# CLP_v1_2_Sch.net
KiCad netlist of a schematic drawn in Altium Designer
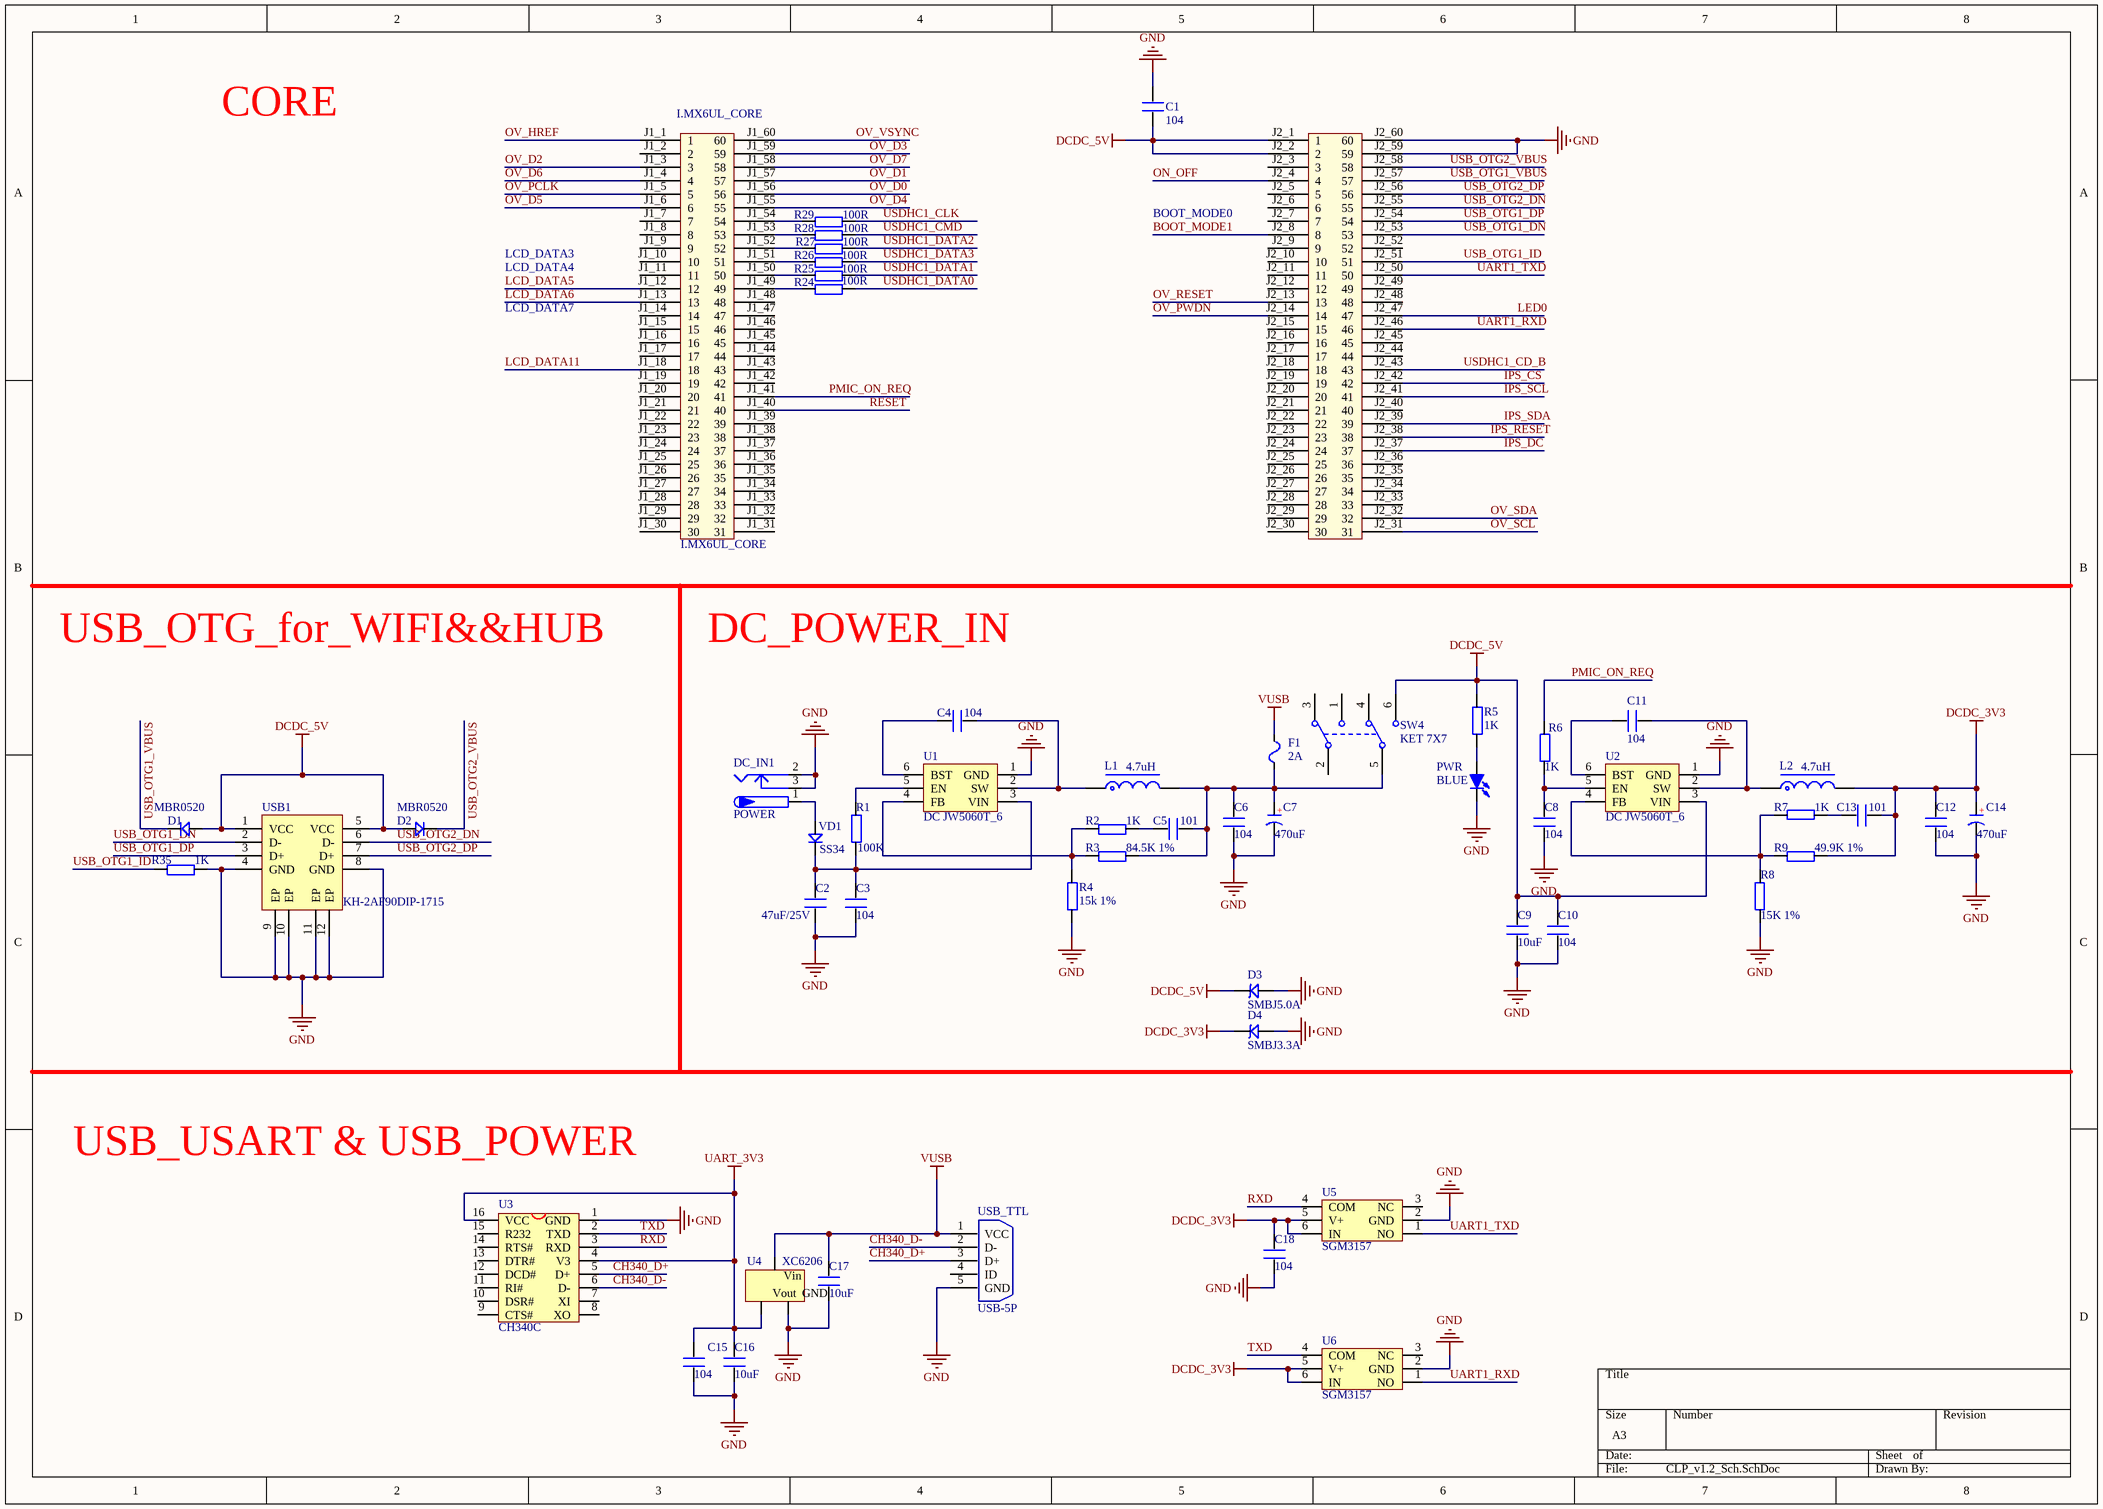
[diagram p0: CLP_v1.2_Sch.SchDoc]

(export (version "E")
  (design (tool "Eeschema 10.0.6"))
  (components
    (comp (ref "C1") (value "104") (footprint "C 0603") (libsource (lib "IMX6UL_ALPHA(底板)_V2.0") (part "C")))
    (comp (ref "C2")
      (value "47uF/25V")
      (footprint "1206")
      (libsource (lib "IMX6UL_ALPHA(底板)_V2.0") (part "C"))
    )
    (comp (ref "C3") (value "104") (footprint "C 0603") (libsource (lib "IMX6UL_ALPHA(底板)_V2.0") (part "C")))
    (comp (ref "C4") (value "104") (footprint "C 0603") (libsource (lib "IMX6UL_ALPHA(底板)_V2.0") (part "C")))
    (comp (ref "C5") (value "101") (footprint "C 0603") (libsource (lib "IMX6UL_ALPHA(底板)_V2.0") (part "C")))
    (comp (ref "C6") (value "104") (footprint "C 0603") (libsource (lib "IMX6UL_ALPHA(底板)_V2.0") (part "C")))
    (comp (ref "C7")
      (value "470uF")
      (footprint "CM D(6.3*7.7)")
      (description "贴片电解电容")
      (fields (field (name "版权归属") "源创客"))
      (libsource (lib "IMX6UL_ALPHA(底板)_V2.0") (part "C-CM"))
    )
    (comp (ref "C8") (value "104") (footprint "C 0603") (libsource (lib "IMX6UL_ALPHA(底板)_V2.0") (part "C")))
    (comp (ref "C9") (value "10uF") (footprint "C 0603") (libsource (lib "IMX6UL_ALPHA(底板)_V2.0") (part "C")))
    (comp (ref "C10") (value "104") (footprint "C 0603") (libsource (lib "IMX6UL_ALPHA(底板)_V2.0") (part "C")))
    (comp (ref "C11") (value "104") (footprint "C 0603") (libsource (lib "IMX6UL_ALPHA(底板)_V2.0") (part "C")))
    (comp (ref "C12") (value "104") (footprint "C 0603") (libsource (lib "IMX6UL_ALPHA(底板)_V2.0") (part "C")))
    (comp (ref "C13") (value "101") (footprint "C 0603") (libsource (lib "IMX6UL_ALPHA(底板)_V2.0") (part "C")))
    (comp (ref "C14")
      (value "470uF")
      (footprint "CM D(6.3*7.7)")
      (description "贴片电解电容")
      (fields (field (name "版权归属") "源创客"))
      (libsource (lib "IMX6UL_ALPHA(底板)_V2.0") (part "C-CM"))
    )
    (comp (ref "C15") (value "104") (footprint "C 0603") (libsource (lib "IMX6UL_ALPHA(底板)_V2.0") (part "C")))
    (comp (ref "C16")
      (value "10uF")
      (footprint "C 0603")
      (libsource (lib "IMX6UL_ALPHA(底板)_V2.0") (part "C"))
    )
    (comp (ref "C17")
      (value "10uF")
      (footprint "C 0603")
      (libsource (lib "IMX6UL_ALPHA(底板)_V2.0") (part "C"))
    )
    (comp (ref "C18") (value "104") (footprint "C 0603") (libsource (lib "IMX6UL_ALPHA(底板)_V2.0") (part "C")))
    (comp (ref "D1")
      (value "MBR0520")
      (footprint "SOD-123F")
      (description "肖特基二极管")
      (fields (field (name "版权归属") "源创客"))
      (libsource (lib "IMX6UL_ALPHA(底板)_V2.0") (part "SS14"))
    )
    (comp (ref "D2")
      (value "MBR0520")
      (footprint "SOD-123F")
      (description "肖特基二极管")
      (fields (field (name "版权归属") "源创客"))
      (libsource (lib "IMX6UL_ALPHA(底板)_V2.0") (part "SS14"))
    )
    (comp (ref "D3")
      (value "SMBJ5.0A")
      (footprint "SMBJ")
      (description "TVS")
      (libsource (lib "IMX6UL_ALPHA(底板)_V2.0") (part "SMBJ"))
    )
    (comp (ref "D4")
      (value "SMBJ3.3A")
      (footprint "SMBJ")
      (description "TVS")
      (libsource (lib "IMX6UL_ALPHA(底板)_V2.0") (part "SMBJ"))
    )
    (comp (ref "DC_IN1")
      (value "POWER")
      (footprint "DC10B")
      (description "低压电源接口")
      (fields (field (name "版权归属") "源创客"))
      (libsource (lib "IMX6UL_ALPHA(底板)_V2.0") (part "P-DC"))
    )
    (comp (ref "F1")
      (value "2A")
      (footprint "FU 1206")
      (description "贴片保险丝")
      (fields (field (name "版权归属") "源创客"))
      (libsource (lib "IMX6UL_ALPHA(底板)_V2.0") (part "FU"))
    )
    (comp (ref "I.MX6UL_CORE")
      (value "I.MX6UL_CORE")
      (footprint "I.MX6UL_CORE")
      (description "I.MX6UL核心板")
      (libsource (lib "IMX6UL_ALPHA(底板)_V2.0") (part "I.MX6UL核心板"))
    )
    (comp (ref "L1")
      (value "4.7uH")
      (footprint "L-SMD-0420")
      (description "功率屏蔽电感")
      (fields (field (name "版权归属") "源创客"))
      (libsource (lib "IMX6UL_ALPHA(底板)_V2.0") (part "L-CDRH"))
    )
    (comp (ref "L2")
      (value "4.7uH")
      (footprint "L-SMD-0420")
      (description "功率屏蔽电感")
      (fields (field (name "版权归属") "源创客"))
      (libsource (lib "IMX6UL_ALPHA(底板)_V2.0") (part "L-CDRH"))
    )
    (comp (ref "PWR")
      (value "BLUE")
      (footprint "LED 0805R")
      (description "贴片LED")
      (fields (field (name "版权归属") "源创客"))
      (libsource (lib "IMX6UL_ALPHA(底板)_V2.0") (part "LED-SMD"))
    )
    (comp (ref "R1") (value "100K") (footprint "R 0603") (libsource (lib "IMX6UL_ALPHA(底板)_V2.0") (part "R")))
    (comp (ref "R2") (value "1K") (footprint "R 0603") (libsource (lib "IMX6UL_ALPHA(底板)_V2.0") (part "R")))
    (comp (ref "R3")
      (value "84.5K 1%")
      (footprint "R 0603")
      (libsource (lib "IMX6UL_ALPHA(底板)_V2.0") (part "R"))
    )
    (comp (ref "R4")
      (value "15k 1%")
      (footprint "R 0603")
      (libsource (lib "IMX6UL_ALPHA(底板)_V2.0") (part "R"))
    )
    (comp (ref "R5") (value "1K") (footprint "R 0603") (libsource (lib "IMX6UL_ALPHA(底板)_V2.0") (part "R")))
    (comp (ref "R6") (value "1K") (footprint "R 0603") (libsource (lib "IMX6UL_ALPHA(底板)_V2.0") (part "R")))
    (comp (ref "R7") (value "1K") (footprint "R 0603") (libsource (lib "IMX6UL_ALPHA(底板)_V2.0") (part "R")))
    (comp (ref "R8")
      (value "15K 1%")
      (footprint "R 0603")
      (libsource (lib "IMX6UL_ALPHA(底板)_V2.0") (part "R"))
    )
    (comp (ref "R9")
      (value "49.9K 1%")
      (footprint "R 0603")
      (libsource (lib "IMX6UL_ALPHA(底板)_V2.0") (part "R"))
    )
    (comp (ref "R24")
      (value "100R")
      (footprint "R 0603")
      (libsource (lib "IMX6UL_ALPHA(底板)_V2.0") (part "R"))
    )
    (comp (ref "R25")
      (value "100R")
      (footprint "R 0603")
      (libsource (lib "IMX6UL_ALPHA(底板)_V2.0") (part "R"))
    )
    (comp (ref "R26")
      (value "100R")
      (footprint "R 0603")
      (libsource (lib "IMX6UL_ALPHA(底板)_V2.0") (part "R"))
    )
    (comp (ref "R27")
      (value "100R")
      (footprint "R 0603")
      (libsource (lib "IMX6UL_ALPHA(底板)_V2.0") (part "R"))
    )
    (comp (ref "R28")
      (value "100R")
      (footprint "R 0603")
      (libsource (lib "IMX6UL_ALPHA(底板)_V2.0") (part "R"))
    )
    (comp (ref "R29")
      (value "100R")
      (footprint "R 0603")
      (libsource (lib "IMX6UL_ALPHA(底板)_V2.0") (part "R"))
    )
    (comp (ref "R35") (value "1K") (footprint "R 0603") (libsource (lib "IMX6UL_ALPHA(底板)_V2.0") (part "R")))
    (comp (ref "SW4")
      (value "KET 7X7")
      (footprint "KFT DIP-7X7")
      (description "7*7自锁开关")
      (fields (field (name "版权归属") "黎明电子style"))
      (libsource (lib "按键_开关") (part "KET 7X7"))
    )
    (comp (ref "U1")
      (value "DC JW5060T_6")
      (footprint "SOT23-6N")
      (description "DC降压芯片")
      (libsource (lib "IMX6UL_ALPHA(底板)_V2.0") (part "DC JW5060T_6"))
    )
    (comp (ref "U2")
      (value "DC JW5060T_6")
      (footprint "SOT23-6N")
      (description "DC降压芯片")
      (libsource (lib "IMX6UL_ALPHA(底板)_V2.0") (part "DC JW5060T_6"))
    )
    (comp (ref "U3")
      (value "CH340C")
      (footprint "SOP16_N")
      (description "USB2UART")
      (libsource (lib "IMX6UL_ALPHA(底板)_V2.0") (part "CH340G"))
    )
    (comp (ref "U4")
      (value "XC6206")
      (footprint "SOT23-3N")
      (description "LDO")
      (libsource (lib "IMX6UL_ALPHA(底板)_V2.0") (part "LDO XC6206"))
    )
    (comp (ref "U5")
      (value "SGM3157")
      (footprint "SOT363-6L")
      (description "单路双掷模拟开关")
      (libsource (lib "IMX6UL_ALPHA(底板)_V2.0") (part "SGM3157"))
    )
    (comp (ref "U6")
      (value "SGM3157")
      (footprint "SOT363-6L")
      (description "单路双掷模拟开关")
      (libsource (lib "IMX6UL_ALPHA(底板)_V2.0") (part "SGM3157"))
    )
    (comp (ref "USB1")
      (value "KH-2AF90DIP-1715")
      (footprint "USB_HOST")
      (description "WIFI && USB_HUB")
      (libsource (lib "CLP_v1.2_SchLib") (part "USB_HOST"))
    )
    (comp (ref "USB_TTL")
      (value "USB-5P")
      (footprint "USB-MINI-A")
      (description "微型USB母座")
      (fields (field (name "版权归属") "源创客"))
      (libsource (lib "IMX6UL_ALPHA(底板)_V2.0") (part "USB-5P"))
    )
    (comp (ref "VD1")
      (value "SS34")
      (footprint "SOD-123F")
      (description "肖特基二极管")
      (fields (field (name "版权归属") "源创客"))
      (libsource (lib "IMX6UL_ALPHA(底板)_V2.0") (part "SS14"))
    )
  )
  (nets
    (net (code "1") (name "/BOOT_MODE1") (class "Default")
      (node (ref "I.MX6UL_CORE") (pin "J2_8") (pinfunction "8_J2_8") (pintype "passive"))
    )
    (net (code "2") (name "/CH340_D+") (class "Default")
      (node (ref "U3") (pin "5") (pinfunction "D+_5") (pintype "passive"))
      (node (ref "USB_TTL") (pin "3") (pinfunction "D+_3") (pintype "passive"))
    )
    (net (code "3") (name "/CH340_D-") (class "Default")
      (node (ref "U3") (pin "6") (pinfunction "D-_6") (pintype "passive"))
      (node (ref "USB_TTL") (pin "2") (pinfunction "D-_2") (pintype "passive"))
    )
    (net (code "4") (name "/IPS_CS") (class "Default")
      (node (ref "I.MX6UL_CORE") (pin "J2_42") (pinfunction "42_J2_42") (pintype "passive"))
    )
    (net (code "5") (name "/IPS_DC") (class "Default")
      (node (ref "I.MX6UL_CORE") (pin "J2_37") (pinfunction "37_J2_37") (pintype "passive"))
    )
    (net (code "6") (name "/IPS_RESET") (class "Default")
      (node (ref "I.MX6UL_CORE") (pin "J2_38") (pinfunction "38_J2_38") (pintype "passive"))
    )
    (net (code "7") (name "/IPS_SCL") (class "Default")
      (node (ref "I.MX6UL_CORE") (pin "J2_41") (pinfunction "41_J2_41") (pintype "passive"))
    )
    (net (code "8") (name "/IPS_SDA") (class "Default")
      (node (ref "I.MX6UL_CORE") (pin "J2_39") (pinfunction "39_J2_39") (pintype "passive"))
    )
    (net (code "9") (name "/LCD_DATA5") (class "Default")
      (node (ref "I.MX6UL_CORE") (pin "J1_12") (pinfunction "12_J1_12") (pintype "passive"))
    )
    (net (code "10") (name "/LCD_DATA6") (class "Default")
      (node (ref "I.MX6UL_CORE") (pin "J1_13") (pinfunction "13_J1_13") (pintype "passive"))
    )
    (net (code "11") (name "/LCD_DATA11") (class "Default")
      (node (ref "I.MX6UL_CORE") (pin "J1_18") (pinfunction "18_J1_18") (pintype "passive"))
    )
    (net (code "12") (name "/LED0") (class "Default")
      (node (ref "I.MX6UL_CORE") (pin "J2_47") (pinfunction "47_J2_47") (pintype "passive"))
    )
    (net (code "13") (name "/ON_OFF") (class "Default")
      (node (ref "I.MX6UL_CORE") (pin "J2_4") (pinfunction "4_J2_4") (pintype "passive"))
    )
    (net (code "14") (name "/OV_D0") (class "Default")
      (node (ref "I.MX6UL_CORE") (pin "J1_56") (pinfunction "56_J1_56") (pintype "passive"))
    )
    (net (code "15") (name "/OV_D1") (class "Default")
      (node (ref "I.MX6UL_CORE") (pin "J1_57") (pinfunction "57_J1_57") (pintype "passive"))
    )
    (net (code "16") (name "/OV_D2") (class "Default")
      (node (ref "I.MX6UL_CORE") (pin "J1_3") (pinfunction "3_J1_3") (pintype "passive"))
    )
    (net (code "17") (name "/OV_D3") (class "Default")
      (node (ref "I.MX6UL_CORE") (pin "J1_59") (pinfunction "59_J1_59") (pintype "passive"))
    )
    (net (code "18") (name "/OV_D4") (class "Default")
      (node (ref "I.MX6UL_CORE") (pin "J1_55") (pinfunction "55_J1_55") (pintype "passive"))
    )
    (net (code "19") (name "/OV_D5") (class "Default")
      (node (ref "I.MX6UL_CORE") (pin "J1_6") (pinfunction "6_J1_6") (pintype "passive"))
    )
    (net (code "20") (name "/OV_D6") (class "Default")
      (node (ref "I.MX6UL_CORE") (pin "J1_4") (pinfunction "4_J1_4") (pintype "passive"))
    )
    (net (code "21") (name "/OV_D7") (class "Default")
      (node (ref "I.MX6UL_CORE") (pin "J1_58") (pinfunction "58_J1_58") (pintype "passive"))
    )
    (net (code "22") (name "/OV_HREF") (class "Default")
      (node (ref "I.MX6UL_CORE") (pin "J1_1") (pinfunction "1_J1_1") (pintype "passive"))
    )
    (net (code "23") (name "/OV_PCLK") (class "Default")
      (node (ref "I.MX6UL_CORE") (pin "J1_5") (pinfunction "5_J1_5") (pintype "passive"))
    )
    (net (code "24") (name "/OV_PWDN") (class "Default")
      (node (ref "I.MX6UL_CORE") (pin "J2_14") (pinfunction "14_J2_14") (pintype "passive"))
    )
    (net (code "25") (name "/OV_RESET") (class "Default")
      (node (ref "I.MX6UL_CORE") (pin "J2_13") (pinfunction "13_J2_13") (pintype "passive"))
    )
    (net (code "26") (name "/OV_SCL") (class "Default")
      (node (ref "I.MX6UL_CORE") (pin "J2_31") (pinfunction "31_J2_31") (pintype "passive"))
    )
    (net (code "27") (name "/OV_SDA") (class "Default")
      (node (ref "I.MX6UL_CORE") (pin "J2_32") (pinfunction "32_J2_32") (pintype "passive"))
    )
    (net (code "28") (name "/OV_VSYNC") (class "Default")
      (node (ref "I.MX6UL_CORE") (pin "J1_60") (pinfunction "60_J1_60") (pintype "passive"))
    )
    (net (code "29") (name "/PMIC_ON_REQ") (class "Default")
      (node (ref "I.MX6UL_CORE") (pin "J1_41") (pinfunction "41_J1_41") (pintype "passive"))
      (node (ref "R6") (pin "2") (pintype "passive"))
    )
    (net (code "30") (name "/RESET") (class "Default")
      (node (ref "I.MX6UL_CORE") (pin "J1_40") (pinfunction "40_J1_40") (pintype "passive"))
    )
    (net (code "31") (name "/RXD") (class "Default")
      (node (ref "U3") (pin "3") (pinfunction "RXD_3") (pintype "passive"))
      (node (ref "U5") (pin "4") (pinfunction "COM_4") (pintype "passive"))
    )
    (net (code "32") (name "/TXD") (class "Default")
      (node (ref "U3") (pin "2") (pinfunction "TXD_2") (pintype "passive"))
      (node (ref "U6") (pin "4") (pinfunction "COM_4") (pintype "passive"))
    )
    (net (code "33") (name "/UART1_RXD") (class "Default")
      (node (ref "I.MX6UL_CORE") (pin "J2_46") (pinfunction "46_J2_46") (pintype "passive"))
      (node (ref "U6") (pin "1") (pinfunction "NO_1") (pintype "passive"))
    )
    (net (code "34") (name "/UART1_TXD") (class "Default")
      (node (ref "I.MX6UL_CORE") (pin "J2_50") (pinfunction "50_J2_50") (pintype "passive"))
      (node (ref "U5") (pin "1") (pinfunction "NO_1") (pintype "passive"))
    )
    (net (code "35") (name "/USB_OTG1_DN") (class "Default")
      (node (ref "I.MX6UL_CORE") (pin "J2_53") (pinfunction "53_J2_53") (pintype "passive"))
      (node (ref "USB1") (pin "2") (pinfunction "D-_2") (pintype "passive"))
    )
    (net (code "36") (name "/USB_OTG1_DP") (class "Default")
      (node (ref "I.MX6UL_CORE") (pin "J2_54") (pinfunction "54_J2_54") (pintype "passive"))
      (node (ref "USB1") (pin "3") (pinfunction "D+_3") (pintype "passive"))
    )
    (net (code "37") (name "/USB_OTG1_ID") (class "Default")
      (node (ref "I.MX6UL_CORE") (pin "J2_51") (pinfunction "51_J2_51") (pintype "passive"))
      (node (ref "R35") (pin "1") (pintype "passive"))
    )
    (net (code "38") (name "/USB_OTG1_VBUS") (class "Default")
      (node (ref "D1") (pin "2") (pinfunction "K_2") (pintype "passive"))
      (node (ref "I.MX6UL_CORE") (pin "J2_57") (pinfunction "57_J2_57") (pintype "passive"))
    )
    (net (code "39") (name "/USB_OTG2_DN") (class "Default")
      (node (ref "I.MX6UL_CORE") (pin "J2_55") (pinfunction "55_J2_55") (pintype "passive"))
      (node (ref "USB1") (pin "6") (pinfunction "D-_6") (pintype "passive"))
    )
    (net (code "40") (name "/USB_OTG2_DP") (class "Default")
      (node (ref "I.MX6UL_CORE") (pin "J2_56") (pinfunction "56_J2_56") (pintype "passive"))
      (node (ref "USB1") (pin "7") (pinfunction "D+_7") (pintype "passive"))
    )
    (net (code "41") (name "/USB_OTG2_VBUS") (class "Default")
      (node (ref "D2") (pin "2") (pinfunction "K_2") (pintype "passive"))
      (node (ref "I.MX6UL_CORE") (pin "J2_58") (pinfunction "58_J2_58") (pintype "passive"))
    )
    (net (code "42") (name "/USDHC1_CD_B") (class "Default")
      (node (ref "I.MX6UL_CORE") (pin "J2_43") (pinfunction "43_J2_43") (pintype "passive"))
    )
    (net (code "43") (name "/USDHC1_CLK") (class "Default") (node (ref "R29") (pin "2") (pintype "passive")))
    (net (code "44") (name "/USDHC1_CMD") (class "Default") (node (ref "R28") (pin "2") (pintype "passive")))
    (net (code "45") (name "/USDHC1_DATA0") (class "Default")
      (node (ref "R24") (pin "2") (pintype "passive"))
    )
    (net (code "46") (name "/USDHC1_DATA1") (class "Default")
      (node (ref "R25") (pin "2") (pintype "passive"))
    )
    (net (code "47") (name "/USDHC1_DATA2") (class "Default")
      (node (ref "R27") (pin "2") (pintype "passive"))
    )
    (net (code "48") (name "/USDHC1_DATA3") (class "Default")
      (node (ref "R26") (pin "2") (pintype "passive"))
    )
    (net (code "49") (name "DCDC_3V3") (class "Default")
      (node (ref "C12") (pin "1") (pintype "passive"))
      (node (ref "C13") (pin "1") (pintype "passive"))
      (node (ref "C14") (pin "1") (pinfunction "A_1") (pintype "passive"))
      (node (ref "C18") (pin "2") (pintype "passive"))
      (node (ref "D4") (pin "2") (pintype "passive"))
      (node (ref "L2") (pin "2") (pinfunction "2_2") (pintype "passive"))
      (node (ref "R9") (pin "2") (pintype "passive"))
      (node (ref "U5") (pin "5") (pinfunction "V+_5") (pintype "passive"))
      (node (ref "U5") (pin "6") (pinfunction "IN_6") (pintype "passive"))
      (node (ref "U6") (pin "5") (pinfunction "V+_5") (pintype "passive"))
      (node (ref "U6") (pin "6") (pinfunction "IN_6") (pintype "passive"))
    )
    (net (code "50") (name "DCDC_5V") (class "Default")
      (node (ref "C1") (pin "1") (pintype "passive"))
      (node (ref "C10") (pin "2") (pintype "passive"))
      (node (ref "C9") (pin "2") (pintype "passive"))
      (node (ref "D1") (pin "1") (pinfunction "A_1") (pintype "passive"))
      (node (ref "D2") (pin "1") (pinfunction "A_1") (pintype "passive"))
      (node (ref "D3") (pin "2") (pintype "passive"))
      (node (ref "I.MX6UL_CORE") (pin "J2_1") (pinfunction "1_J2_1") (pintype "passive"))
      (node (ref "I.MX6UL_CORE") (pin "J2_2") (pinfunction "2_J2_2") (pintype "passive"))
      (node (ref "R5") (pin "2") (pintype "passive"))
      (node (ref "SW4") (pin "6") (pinfunction "NC2_6") (pintype "passive"))
      (node (ref "U2") (pin "3") (pinfunction "VIN_3") (pintype "passive"))
      (node (ref "USB1") (pin "1") (pinfunction "VCC_1") (pintype "passive"))
      (node (ref "USB1") (pin "5") (pinfunction "VCC_5") (pintype "passive"))
    )
    (net (code "51") (name "GND") (class "Default")
      (node (ref "C1") (pin "2") (pintype "passive"))
      (node (ref "C10") (pin "1") (pintype "passive"))
      (node (ref "C12") (pin "2") (pintype "passive"))
      (node (ref "C14") (pin "2") (pinfunction "K_2") (pintype "passive"))
      (node (ref "C15") (pin "1") (pintype "passive"))
      (node (ref "C16") (pin "1") (pintype "passive"))
      (node (ref "C17") (pin "1") (pintype "passive"))
      (node (ref "C18") (pin "1") (pintype "passive"))
      (node (ref "C2") (pin "2") (pintype "passive"))
      (node (ref "C3") (pin "2") (pintype "passive"))
      (node (ref "C6") (pin "1") (pintype "passive"))
      (node (ref "C7") (pin "2") (pinfunction "K_2") (pintype "passive"))
      (node (ref "C8") (pin "1") (pintype "passive"))
      (node (ref "C9") (pin "1") (pintype "passive"))
      (node (ref "D3") (pin "1") (pintype "passive"))
      (node (ref "D4") (pin "1") (pintype "passive"))
      (node (ref "DC_IN1") (pin "2") (pintype "power_in"))
      (node (ref "DC_IN1") (pin "3") (pintype "power_in"))
      (node (ref "I.MX6UL_CORE") (pin "J2_59") (pinfunction "59_J2_59") (pintype "passive"))
      (node (ref "I.MX6UL_CORE") (pin "J2_60") (pinfunction "60_J2_60") (pintype "passive"))
      (node (ref "PWR") (pin "2") (pinfunction "K_2") (pintype "passive"))
      (node (ref "R35") (pin "2") (pintype "passive"))
      (node (ref "R4") (pin "1") (pintype "passive"))
      (node (ref "R8") (pin "2") (pintype "passive"))
      (node (ref "U1") (pin "1") (pinfunction "GND_1") (pintype "passive"))
      (node (ref "U2") (pin "1") (pinfunction "GND_1") (pintype "passive"))
      (node (ref "U3") (pin "1") (pinfunction "GND_1") (pintype "passive"))
      (node (ref "U4") (pin "1") (pinfunction "GND_1") (pintype "passive"))
      (node (ref "U5") (pin "2") (pinfunction "GND_2") (pintype "passive"))
      (node (ref "U6") (pin "2") (pinfunction "GND_2") (pintype "passive"))
      (node (ref "USB1") (pin "10") (pinfunction "EP_10") (pintype "passive"))
      (node (ref "USB1") (pin "11") (pinfunction "EP_11") (pintype "passive"))
      (node (ref "USB1") (pin "12") (pinfunction "EP_12") (pintype "passive"))
      (node (ref "USB1") (pin "4") (pinfunction "GND_4") (pintype "passive"))
      (node (ref "USB1") (pin "8") (pinfunction "GND_8") (pintype "passive"))
      (node (ref "USB1") (pin "9") (pinfunction "EP_9") (pintype "passive"))
      (node (ref "USB_TTL") (pin "5") (pinfunction "GND_5") (pintype "passive"))
    )
    (net (code "52") (name "Net-(C5-Pad1)") (class "Default")
      (node (ref "C5") (pin "1") (pintype "passive"))
      (node (ref "R2") (pin "2") (pintype "passive"))
    )
    (net (code "53") (name "Net-(C7-A)") (class "Default")
      (node (ref "C5") (pin "2") (pintype "passive"))
      (node (ref "C6") (pin "2") (pintype "passive"))
      (node (ref "C7") (pin "1") (pinfunction "A_1") (pintype "passive"))
      (node (ref "F1") (pin "1") (pinfunction "1_1") (pintype "passive"))
      (node (ref "L1") (pin "2") (pinfunction "2_2") (pintype "passive"))
      (node (ref "R3") (pin "2") (pintype "passive"))
      (node (ref "SW4") (pin "5") (pinfunction "COM2_5") (pintype "passive"))
    )
    (net (code "54") (name "Net-(C13-Pad2)") (class "Default")
      (node (ref "C13") (pin "2") (pintype "passive"))
      (node (ref "R7") (pin "1") (pintype "passive"))
    )
    (net (code "55") (name "Net-(I.MX6UL_CORE-49-PadJ1_49)") (class "Default")
      (node (ref "I.MX6UL_CORE") (pin "J1_49") (pinfunction "49_J1_49") (pintype "passive"))
      (node (ref "R24") (pin "1") (pintype "passive"))
    )
    (net (code "56") (name "Net-(I.MX6UL_CORE-50-PadJ1_50)") (class "Default")
      (node (ref "I.MX6UL_CORE") (pin "J1_50") (pinfunction "50_J1_50") (pintype "passive"))
      (node (ref "R25") (pin "1") (pintype "passive"))
    )
    (net (code "57") (name "Net-(I.MX6UL_CORE-51-PadJ1_51)") (class "Default")
      (node (ref "I.MX6UL_CORE") (pin "J1_51") (pinfunction "51_J1_51") (pintype "passive"))
      (node (ref "R26") (pin "1") (pintype "passive"))
    )
    (net (code "58") (name "Net-(I.MX6UL_CORE-52-PadJ1_52)") (class "Default")
      (node (ref "I.MX6UL_CORE") (pin "J1_52") (pinfunction "52_J1_52") (pintype "passive"))
      (node (ref "R27") (pin "1") (pintype "passive"))
    )
    (net (code "59") (name "Net-(I.MX6UL_CORE-53-PadJ1_53)") (class "Default")
      (node (ref "I.MX6UL_CORE") (pin "J1_53") (pinfunction "53_J1_53") (pintype "passive"))
      (node (ref "R28") (pin "1") (pintype "passive"))
    )
    (net (code "60") (name "Net-(I.MX6UL_CORE-54-PadJ1_54)") (class "Default")
      (node (ref "I.MX6UL_CORE") (pin "J1_54") (pinfunction "54_J1_54") (pintype "passive"))
      (node (ref "R29") (pin "1") (pintype "passive"))
    )
    (net (code "61") (name "Net-(PWR-A)") (class "Default")
      (node (ref "PWR") (pin "1") (pinfunction "A_1") (pintype "passive"))
      (node (ref "R5") (pin "1") (pintype "passive"))
    )
    (net (code "62") (name "Net-(U1-BST)") (class "Default")
      (node (ref "C4") (pin "1") (pintype "passive"))
      (node (ref "U1") (pin "6") (pinfunction "BST_6") (pintype "passive"))
    )
    (net (code "63") (name "Net-(U1-EN)") (class "Default")
      (node (ref "R1") (pin "2") (pintype "passive"))
      (node (ref "U1") (pin "5") (pinfunction "EN_5") (pintype "passive"))
    )
    (net (code "64") (name "Net-(U1-FB)") (class "Default")
      (node (ref "R2") (pin "1") (pintype "passive"))
      (node (ref "R3") (pin "1") (pintype "passive"))
      (node (ref "R4") (pin "2") (pintype "passive"))
      (node (ref "U1") (pin "4") (pinfunction "FB_4") (pintype "passive"))
    )
    (net (code "65") (name "Net-(U1-SW)") (class "Default")
      (node (ref "C4") (pin "2") (pintype "passive"))
      (node (ref "L1") (pin "1") (pinfunction "1_1") (pintype "passive"))
      (node (ref "U1") (pin "2") (pinfunction "SW_2") (pintype "passive"))
    )
    (net (code "66") (name "Net-(U1-VIN)") (class "Default")
      (node (ref "C2") (pin "1") (pintype "passive"))
      (node (ref "C3") (pin "1") (pintype "passive"))
      (node (ref "R1") (pin "1") (pintype "passive"))
      (node (ref "U1") (pin "3") (pinfunction "VIN_3") (pintype "passive"))
      (node (ref "VD1") (pin "2") (pinfunction "K_2") (pintype "passive"))
    )
    (net (code "67") (name "Net-(U2-BST)") (class "Default")
      (node (ref "C11") (pin "2") (pintype "passive"))
      (node (ref "U2") (pin "6") (pinfunction "BST_6") (pintype "passive"))
    )
    (net (code "68") (name "Net-(U2-EN)") (class "Default")
      (node (ref "C8") (pin "2") (pintype "passive"))
      (node (ref "R6") (pin "1") (pintype "passive"))
      (node (ref "U2") (pin "5") (pinfunction "EN_5") (pintype "passive"))
    )
    (net (code "69") (name "Net-(U2-FB)") (class "Default")
      (node (ref "R7") (pin "2") (pintype "passive"))
      (node (ref "R8") (pin "1") (pintype "passive"))
      (node (ref "R9") (pin "1") (pintype "passive"))
      (node (ref "U2") (pin "4") (pinfunction "FB_4") (pintype "passive"))
    )
    (net (code "70") (name "Net-(U2-SW)") (class "Default")
      (node (ref "C11") (pin "1") (pintype "passive"))
      (node (ref "L2") (pin "1") (pinfunction "1_1") (pintype "passive"))
      (node (ref "U2") (pin "2") (pinfunction "SW_2") (pintype "passive"))
    )
    (net (code "71") (name "Net-(VD1-A)") (class "Default")
      (node (ref "DC_IN1") (pin "1") (pintype "power_in"))
      (node (ref "VD1") (pin "1") (pinfunction "A_1") (pintype "passive"))
    )
    (net (code "72") (name "UART_3V3") (class "Default")
      (node (ref "C15") (pin "2") (pintype "passive"))
      (node (ref "C16") (pin "2") (pintype "passive"))
      (node (ref "U3") (pin "16") (pinfunction "VCC_16") (pintype "passive"))
      (node (ref "U3") (pin "4") (pinfunction "V3_4") (pintype "passive"))
      (node (ref "U4") (pin "2") (pinfunction "Vout_2") (pintype "passive"))
    )
    (net (code "73") (name "VUSB") (class "Default")
      (node (ref "C17") (pin "2") (pintype "passive"))
      (node (ref "F1") (pin "2") (pinfunction "2_2") (pintype "passive"))
      (node (ref "U4") (pin "3") (pinfunction "Vin_3") (pintype "passive"))
      (node (ref "USB_TTL") (pin "1") (pinfunction "VCC_1") (pintype "passive"))
    )
    (net (code "74") (name "unconnected-(I.MX6UL_CORE-2-PadJ1_2)") (class "Default")
      (node (ref "I.MX6UL_CORE") (pin "J1_2") (pinfunction "2_J1_2") (pintype "passive"))
    )
    (net (code "75") (name "unconnected-(I.MX6UL_CORE-3-PadJ2_3)") (class "Default")
      (node (ref "I.MX6UL_CORE") (pin "J2_3") (pinfunction "3_J2_3") (pintype "passive"))
    )
    (net (code "76") (name "unconnected-(I.MX6UL_CORE-5-PadJ2_5)") (class "Default")
      (node (ref "I.MX6UL_CORE") (pin "J2_5") (pinfunction "5_J2_5") (pintype "passive"))
    )
    (net (code "77") (name "unconnected-(I.MX6UL_CORE-6-PadJ2_6)") (class "Default")
      (node (ref "I.MX6UL_CORE") (pin "J2_6") (pinfunction "6_J2_6") (pintype "passive"))
    )
    (net (code "78") (name "unconnected-(I.MX6UL_CORE-7-PadJ1_7)") (class "Default")
      (node (ref "I.MX6UL_CORE") (pin "J1_7") (pinfunction "7_J1_7") (pintype "passive"))
    )
    (net (code "79") (name "unconnected-(I.MX6UL_CORE-7-PadJ2_7)") (class "Default")
      (node (ref "I.MX6UL_CORE") (pin "J2_7") (pinfunction "7_J2_7") (pintype "passive"))
    )
    (net (code "80") (name "unconnected-(I.MX6UL_CORE-8-PadJ1_8)") (class "Default")
      (node (ref "I.MX6UL_CORE") (pin "J1_8") (pinfunction "8_J1_8") (pintype "passive"))
    )
    (net (code "81") (name "unconnected-(I.MX6UL_CORE-9-PadJ1_9)") (class "Default")
      (node (ref "I.MX6UL_CORE") (pin "J1_9") (pinfunction "9_J1_9") (pintype "passive"))
    )
    (net (code "82") (name "unconnected-(I.MX6UL_CORE-9-PadJ2_9)") (class "Default")
      (node (ref "I.MX6UL_CORE") (pin "J2_9") (pinfunction "9_J2_9") (pintype "passive"))
    )
    (net (code "83") (name "unconnected-(I.MX6UL_CORE-10-PadJ1_10)") (class "Default")
      (node (ref "I.MX6UL_CORE") (pin "J1_10") (pinfunction "10_J1_10") (pintype "passive"))
    )
    (net (code "84") (name "unconnected-(I.MX6UL_CORE-10-PadJ2_10)") (class "Default")
      (node (ref "I.MX6UL_CORE") (pin "J2_10") (pinfunction "10_J2_10") (pintype "passive"))
    )
    (net (code "85") (name "unconnected-(I.MX6UL_CORE-11-PadJ1_11)") (class "Default")
      (node (ref "I.MX6UL_CORE") (pin "J1_11") (pinfunction "11_J1_11") (pintype "passive"))
    )
    (net (code "86") (name "unconnected-(I.MX6UL_CORE-11-PadJ2_11)") (class "Default")
      (node (ref "I.MX6UL_CORE") (pin "J2_11") (pinfunction "11_J2_11") (pintype "passive"))
    )
    (net (code "87") (name "unconnected-(I.MX6UL_CORE-12-PadJ2_12)") (class "Default")
      (node (ref "I.MX6UL_CORE") (pin "J2_12") (pinfunction "12_J2_12") (pintype "passive"))
    )
    (net (code "88") (name "unconnected-(I.MX6UL_CORE-14-PadJ1_14)") (class "Default")
      (node (ref "I.MX6UL_CORE") (pin "J1_14") (pinfunction "14_J1_14") (pintype "passive"))
    )
    (net (code "89") (name "unconnected-(I.MX6UL_CORE-15-PadJ1_15)") (class "Default")
      (node (ref "I.MX6UL_CORE") (pin "J1_15") (pinfunction "15_J1_15") (pintype "passive"))
    )
    (net (code "90") (name "unconnected-(I.MX6UL_CORE-15-PadJ2_15)") (class "Default")
      (node (ref "I.MX6UL_CORE") (pin "J2_15") (pinfunction "15_J2_15") (pintype "passive"))
    )
    (net (code "91") (name "unconnected-(I.MX6UL_CORE-16-PadJ1_16)") (class "Default")
      (node (ref "I.MX6UL_CORE") (pin "J1_16") (pinfunction "16_J1_16") (pintype "passive"))
    )
    (net (code "92") (name "unconnected-(I.MX6UL_CORE-16-PadJ2_16)") (class "Default")
      (node (ref "I.MX6UL_CORE") (pin "J2_16") (pinfunction "16_J2_16") (pintype "passive"))
    )
    (net (code "93") (name "unconnected-(I.MX6UL_CORE-17-PadJ1_17)") (class "Default")
      (node (ref "I.MX6UL_CORE") (pin "J1_17") (pinfunction "17_J1_17") (pintype "passive"))
    )
    (net (code "94") (name "unconnected-(I.MX6UL_CORE-17-PadJ2_17)") (class "Default")
      (node (ref "I.MX6UL_CORE") (pin "J2_17") (pinfunction "17_J2_17") (pintype "passive"))
    )
    (net (code "95") (name "unconnected-(I.MX6UL_CORE-18-PadJ2_18)") (class "Default")
      (node (ref "I.MX6UL_CORE") (pin "J2_18") (pinfunction "18_J2_18") (pintype "passive"))
    )
    (net (code "96") (name "unconnected-(I.MX6UL_CORE-19-PadJ1_19)") (class "Default")
      (node (ref "I.MX6UL_CORE") (pin "J1_19") (pinfunction "19_J1_19") (pintype "passive"))
    )
    (net (code "97") (name "unconnected-(I.MX6UL_CORE-19-PadJ2_19)") (class "Default")
      (node (ref "I.MX6UL_CORE") (pin "J2_19") (pinfunction "19_J2_19") (pintype "passive"))
    )
    (net (code "98") (name "unconnected-(I.MX6UL_CORE-20-PadJ1_20)") (class "Default")
      (node (ref "I.MX6UL_CORE") (pin "J1_20") (pinfunction "20_J1_20") (pintype "passive"))
    )
    (net (code "99") (name "unconnected-(I.MX6UL_CORE-20-PadJ2_20)") (class "Default")
      (node (ref "I.MX6UL_CORE") (pin "J2_20") (pinfunction "20_J2_20") (pintype "passive"))
    )
    (net (code "100") (name "unconnected-(I.MX6UL_CORE-21-PadJ1_21)") (class "Default")
      (node (ref "I.MX6UL_CORE") (pin "J1_21") (pinfunction "21_J1_21") (pintype "passive"))
    )
    (net (code "101") (name "unconnected-(I.MX6UL_CORE-21-PadJ2_21)") (class "Default")
      (node (ref "I.MX6UL_CORE") (pin "J2_21") (pinfunction "21_J2_21") (pintype "passive"))
    )
    (net (code "102") (name "unconnected-(I.MX6UL_CORE-22-PadJ1_22)") (class "Default")
      (node (ref "I.MX6UL_CORE") (pin "J1_22") (pinfunction "22_J1_22") (pintype "passive"))
    )
    (net (code "103") (name "unconnected-(I.MX6UL_CORE-22-PadJ2_22)") (class "Default")
      (node (ref "I.MX6UL_CORE") (pin "J2_22") (pinfunction "22_J2_22") (pintype "passive"))
    )
    (net (code "104") (name "unconnected-(I.MX6UL_CORE-23-PadJ1_23)") (class "Default")
      (node (ref "I.MX6UL_CORE") (pin "J1_23") (pinfunction "23_J1_23") (pintype "passive"))
    )
    (net (code "105") (name "unconnected-(I.MX6UL_CORE-23-PadJ2_23)") (class "Default")
      (node (ref "I.MX6UL_CORE") (pin "J2_23") (pinfunction "23_J2_23") (pintype "passive"))
    )
    (net (code "106") (name "unconnected-(I.MX6UL_CORE-24-PadJ1_24)") (class "Default")
      (node (ref "I.MX6UL_CORE") (pin "J1_24") (pinfunction "24_J1_24") (pintype "passive"))
    )
    (net (code "107") (name "unconnected-(I.MX6UL_CORE-24-PadJ2_24)") (class "Default")
      (node (ref "I.MX6UL_CORE") (pin "J2_24") (pinfunction "24_J2_24") (pintype "passive"))
    )
    (net (code "108") (name "unconnected-(I.MX6UL_CORE-25-PadJ1_25)") (class "Default")
      (node (ref "I.MX6UL_CORE") (pin "J1_25") (pinfunction "25_J1_25") (pintype "passive"))
    )
    (net (code "109") (name "unconnected-(I.MX6UL_CORE-25-PadJ2_25)") (class "Default")
      (node (ref "I.MX6UL_CORE") (pin "J2_25") (pinfunction "25_J2_25") (pintype "passive"))
    )
    (net (code "110") (name "unconnected-(I.MX6UL_CORE-26-PadJ1_26)") (class "Default")
      (node (ref "I.MX6UL_CORE") (pin "J1_26") (pinfunction "26_J1_26") (pintype "passive"))
    )
    (net (code "111") (name "unconnected-(I.MX6UL_CORE-26-PadJ2_26)") (class "Default")
      (node (ref "I.MX6UL_CORE") (pin "J2_26") (pinfunction "26_J2_26") (pintype "passive"))
    )
    (net (code "112") (name "unconnected-(I.MX6UL_CORE-27-PadJ1_27)") (class "Default")
      (node (ref "I.MX6UL_CORE") (pin "J1_27") (pinfunction "27_J1_27") (pintype "passive"))
    )
    (net (code "113") (name "unconnected-(I.MX6UL_CORE-27-PadJ2_27)") (class "Default")
      (node (ref "I.MX6UL_CORE") (pin "J2_27") (pinfunction "27_J2_27") (pintype "passive"))
    )
    (net (code "114") (name "unconnected-(I.MX6UL_CORE-28-PadJ1_28)") (class "Default")
      (node (ref "I.MX6UL_CORE") (pin "J1_28") (pinfunction "28_J1_28") (pintype "passive"))
    )
    (net (code "115") (name "unconnected-(I.MX6UL_CORE-28-PadJ2_28)") (class "Default")
      (node (ref "I.MX6UL_CORE") (pin "J2_28") (pinfunction "28_J2_28") (pintype "passive"))
    )
    (net (code "116") (name "unconnected-(I.MX6UL_CORE-29-PadJ1_29)") (class "Default")
      (node (ref "I.MX6UL_CORE") (pin "J1_29") (pinfunction "29_J1_29") (pintype "passive"))
    )
    (net (code "117") (name "unconnected-(I.MX6UL_CORE-29-PadJ2_29)") (class "Default")
      (node (ref "I.MX6UL_CORE") (pin "J2_29") (pinfunction "29_J2_29") (pintype "passive"))
    )
    (net (code "118") (name "unconnected-(I.MX6UL_CORE-30-PadJ1_30)") (class "Default")
      (node (ref "I.MX6UL_CORE") (pin "J1_30") (pinfunction "30_J1_30") (pintype "passive"))
    )
    (net (code "119") (name "unconnected-(I.MX6UL_CORE-30-PadJ2_30)") (class "Default")
      (node (ref "I.MX6UL_CORE") (pin "J2_30") (pinfunction "30_J2_30") (pintype "passive"))
    )
    (net (code "120") (name "unconnected-(I.MX6UL_CORE-31-PadJ1_31)") (class "Default")
      (node (ref "I.MX6UL_CORE") (pin "J1_31") (pinfunction "31_J1_31") (pintype "passive"))
    )
    (net (code "121") (name "unconnected-(I.MX6UL_CORE-32-PadJ1_32)") (class "Default")
      (node (ref "I.MX6UL_CORE") (pin "J1_32") (pinfunction "32_J1_32") (pintype "passive"))
    )
    (net (code "122") (name "unconnected-(I.MX6UL_CORE-33-PadJ1_33)") (class "Default")
      (node (ref "I.MX6UL_CORE") (pin "J1_33") (pinfunction "33_J1_33") (pintype "passive"))
    )
    (net (code "123") (name "unconnected-(I.MX6UL_CORE-33-PadJ2_33)") (class "Default")
      (node (ref "I.MX6UL_CORE") (pin "J2_33") (pinfunction "33_J2_33") (pintype "passive"))
    )
    (net (code "124") (name "unconnected-(I.MX6UL_CORE-34-PadJ1_34)") (class "Default")
      (node (ref "I.MX6UL_CORE") (pin "J1_34") (pinfunction "34_J1_34") (pintype "passive"))
    )
    (net (code "125") (name "unconnected-(I.MX6UL_CORE-34-PadJ2_34)") (class "Default")
      (node (ref "I.MX6UL_CORE") (pin "J2_34") (pinfunction "34_J2_34") (pintype "passive"))
    )
    (net (code "126") (name "unconnected-(I.MX6UL_CORE-35-PadJ1_35)") (class "Default")
      (node (ref "I.MX6UL_CORE") (pin "J1_35") (pinfunction "35_J1_35") (pintype "passive"))
    )
    (net (code "127") (name "unconnected-(I.MX6UL_CORE-35-PadJ2_35)") (class "Default")
      (node (ref "I.MX6UL_CORE") (pin "J2_35") (pinfunction "35_J2_35") (pintype "passive"))
    )
    (net (code "128") (name "unconnected-(I.MX6UL_CORE-36-PadJ1_36)") (class "Default")
      (node (ref "I.MX6UL_CORE") (pin "J1_36") (pinfunction "36_J1_36") (pintype "passive"))
    )
    (net (code "129") (name "unconnected-(I.MX6UL_CORE-36-PadJ2_36)") (class "Default")
      (node (ref "I.MX6UL_CORE") (pin "J2_36") (pinfunction "36_J2_36") (pintype "passive"))
    )
    (net (code "130") (name "unconnected-(I.MX6UL_CORE-37-PadJ1_37)") (class "Default")
      (node (ref "I.MX6UL_CORE") (pin "J1_37") (pinfunction "37_J1_37") (pintype "passive"))
    )
    (net (code "131") (name "unconnected-(I.MX6UL_CORE-38-PadJ1_38)") (class "Default")
      (node (ref "I.MX6UL_CORE") (pin "J1_38") (pinfunction "38_J1_38") (pintype "passive"))
    )
    (net (code "132") (name "unconnected-(I.MX6UL_CORE-39-PadJ1_39)") (class "Default")
      (node (ref "I.MX6UL_CORE") (pin "J1_39") (pinfunction "39_J1_39") (pintype "passive"))
    )
    (net (code "133") (name "unconnected-(I.MX6UL_CORE-40-PadJ2_40)") (class "Default")
      (node (ref "I.MX6UL_CORE") (pin "J2_40") (pinfunction "40_J2_40") (pintype "passive"))
    )
    (net (code "134") (name "unconnected-(I.MX6UL_CORE-42-PadJ1_42)") (class "Default")
      (node (ref "I.MX6UL_CORE") (pin "J1_42") (pinfunction "42_J1_42") (pintype "passive"))
    )
    (net (code "135") (name "unconnected-(I.MX6UL_CORE-43-PadJ1_43)") (class "Default")
      (node (ref "I.MX6UL_CORE") (pin "J1_43") (pinfunction "43_J1_43") (pintype "passive"))
    )
    (net (code "136") (name "unconnected-(I.MX6UL_CORE-44-PadJ1_44)") (class "Default")
      (node (ref "I.MX6UL_CORE") (pin "J1_44") (pinfunction "44_J1_44") (pintype "passive"))
    )
    (net (code "137") (name "unconnected-(I.MX6UL_CORE-44-PadJ2_44)") (class "Default")
      (node (ref "I.MX6UL_CORE") (pin "J2_44") (pinfunction "44_J2_44") (pintype "passive"))
    )
    (net (code "138") (name "unconnected-(I.MX6UL_CORE-45-PadJ1_45)") (class "Default")
      (node (ref "I.MX6UL_CORE") (pin "J1_45") (pinfunction "45_J1_45") (pintype "passive"))
    )
    (net (code "139") (name "unconnected-(I.MX6UL_CORE-45-PadJ2_45)") (class "Default")
      (node (ref "I.MX6UL_CORE") (pin "J2_45") (pinfunction "45_J2_45") (pintype "passive"))
    )
    (net (code "140") (name "unconnected-(I.MX6UL_CORE-46-PadJ1_46)") (class "Default")
      (node (ref "I.MX6UL_CORE") (pin "J1_46") (pinfunction "46_J1_46") (pintype "passive"))
    )
    (net (code "141") (name "unconnected-(I.MX6UL_CORE-47-PadJ1_47)") (class "Default")
      (node (ref "I.MX6UL_CORE") (pin "J1_47") (pinfunction "47_J1_47") (pintype "passive"))
    )
    (net (code "142") (name "unconnected-(I.MX6UL_CORE-48-PadJ1_48)") (class "Default")
      (node (ref "I.MX6UL_CORE") (pin "J1_48") (pinfunction "48_J1_48") (pintype "passive"))
    )
    (net (code "143") (name "unconnected-(I.MX6UL_CORE-48-PadJ2_48)") (class "Default")
      (node (ref "I.MX6UL_CORE") (pin "J2_48") (pinfunction "48_J2_48") (pintype "passive"))
    )
    (net (code "144") (name "unconnected-(I.MX6UL_CORE-49-PadJ2_49)") (class "Default")
      (node (ref "I.MX6UL_CORE") (pin "J2_49") (pinfunction "49_J2_49") (pintype "passive"))
    )
    (net (code "145") (name "unconnected-(I.MX6UL_CORE-52-PadJ2_52)") (class "Default")
      (node (ref "I.MX6UL_CORE") (pin "J2_52") (pinfunction "52_J2_52") (pintype "passive"))
    )
    (net (code "146") (name "unconnected-(SW4-COM2-Pad2)") (class "Default")
      (node (ref "SW4") (pin "2") (pinfunction "COM2_2") (pintype "passive"))
    )
    (net (code "147") (name "unconnected-(SW4-NC1-Pad1)") (class "Default")
      (node (ref "SW4") (pin "1") (pinfunction "NC1_1") (pintype "passive"))
    )
    (net (code "148") (name "unconnected-(SW4-NO1-Pad3)") (class "Default")
      (node (ref "SW4") (pin "3") (pinfunction "NO1_3") (pintype "passive"))
    )
    (net (code "149") (name "unconnected-(SW4-NO2-Pad4)") (class "Default")
      (node (ref "SW4") (pin "4") (pinfunction "NO2_4") (pintype "passive"))
    )
    (net (code "150") (name "unconnected-(U3-CTS#-Pad9)") (class "Default")
      (node (ref "U3") (pin "9") (pinfunction "CTS#_9") (pintype "passive"))
    )
    (net (code "151") (name "unconnected-(U3-DCD#-Pad12)") (class "Default")
      (node (ref "U3") (pin "12") (pinfunction "DCD#_12") (pintype "passive"))
    )
    (net (code "152") (name "unconnected-(U3-DSR#-Pad10)") (class "Default")
      (node (ref "U3") (pin "10") (pinfunction "DSR#_10") (pintype "passive"))
    )
    (net (code "153") (name "unconnected-(U3-DTR#-Pad13)") (class "Default")
      (node (ref "U3") (pin "13") (pinfunction "DTR#_13") (pintype "passive"))
    )
    (net (code "154") (name "unconnected-(U3-R232-Pad15)") (class "Default")
      (node (ref "U3") (pin "15") (pinfunction "R232_15") (pintype "passive"))
    )
    (net (code "155") (name "unconnected-(U3-RI#-Pad11)") (class "Default")
      (node (ref "U3") (pin "11") (pinfunction "RI#_11") (pintype "passive"))
    )
    (net (code "156") (name "unconnected-(U3-RTS#-Pad14)") (class "Default")
      (node (ref "U3") (pin "14") (pinfunction "RTS#_14") (pintype "passive"))
    )
    (net (code "157") (name "unconnected-(U3-XI-Pad7)") (class "Default")
      (node (ref "U3") (pin "7") (pinfunction "XI_7") (pintype "passive"))
    )
    (net (code "158") (name "unconnected-(U3-XO-Pad8)") (class "Default")
      (node (ref "U3") (pin "8") (pinfunction "XO_8") (pintype "passive"))
    )
    (net (code "159") (name "unconnected-(U5-NC-Pad3)") (class "Default")
      (node (ref "U5") (pin "3") (pinfunction "NC_3") (pintype "passive"))
    )
    (net (code "160") (name "unconnected-(U6-NC-Pad3)") (class "Default")
      (node (ref "U6") (pin "3") (pinfunction "NC_3") (pintype "passive"))
    )
    (net (code "161") (name "unconnected-(USB_TTL-ID-Pad4)") (class "Default")
      (node (ref "USB_TTL") (pin "4") (pinfunction "ID_4") (pintype "passive"))
    )
  )
)
